# DeckardsHelper.net
KiCad netlist of a schematic drawn in EAGLE
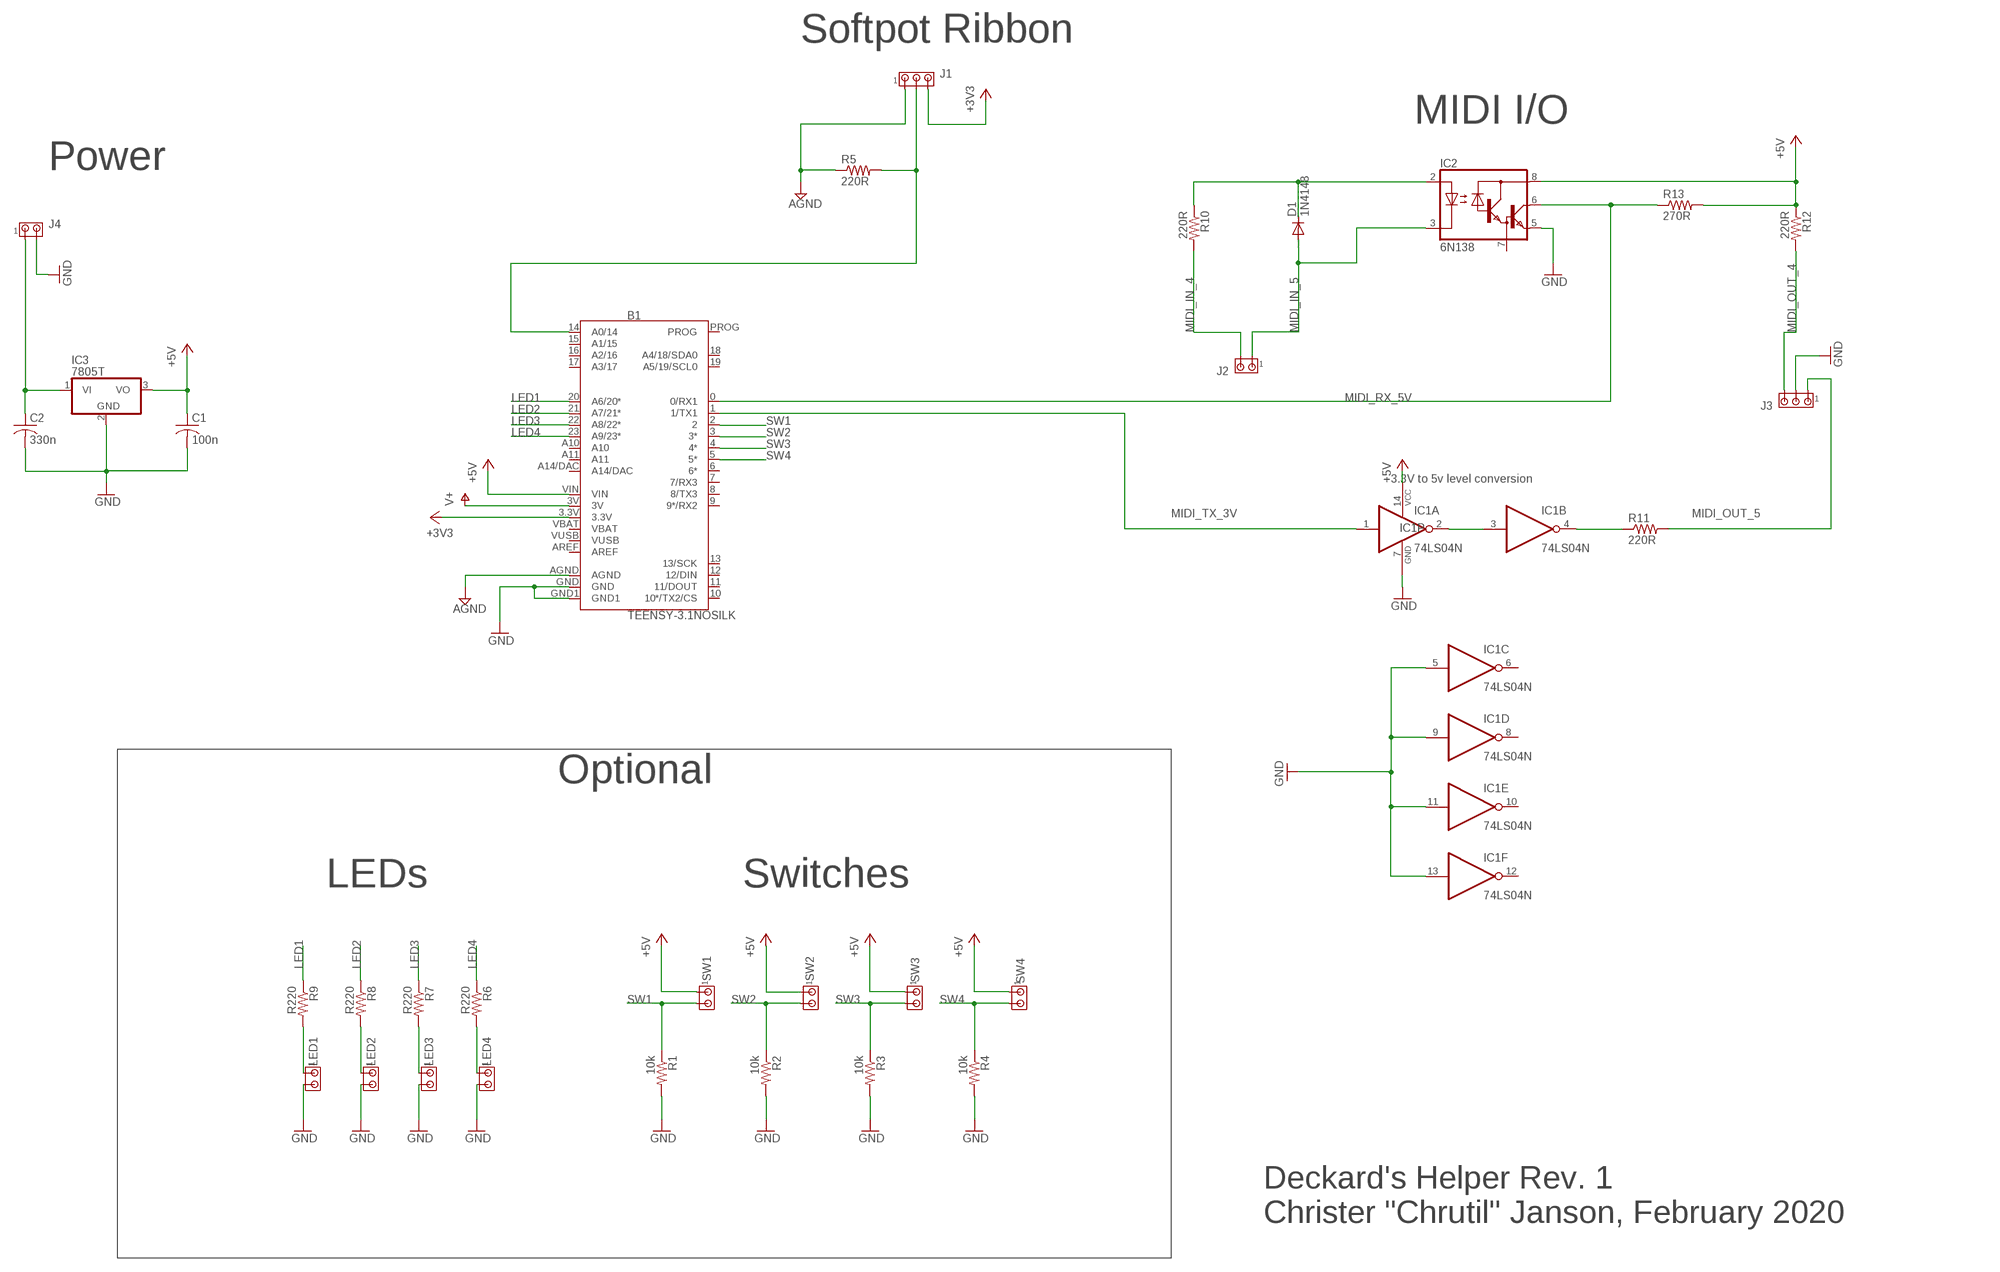
[diagram p0: schematic, sheet 1]

(export (version "E")
  (design (tool "Eeschema 10.0.6"))
  (components
    (comp (ref "B1")
      (value "TEENSY-3.1NOSILK")
      (footprint "eagle-import:TEENSY-3.1_NOSILK")
      (libsource (lib "eagle-import") (part "TEENSY-3.1NOSILK"))
    )
    (comp (ref "C1")
      (value "100n")
      (footprint "eagle-import:C025-025X050")
      (libsource (lib "eagle-import") (part "C-US025-025X050"))
    )
    (comp (ref "C2")
      (value "330n")
      (footprint "eagle-import:C025-025X050")
      (libsource (lib "eagle-import") (part "C-US025-025X050"))
    )
    (comp (ref "D1")
      (value "1N4148")
      (footprint "eagle-import:DO35-7")
      (libsource (lib "eagle-import") (part "1N4148DO35-7"))
    )
    (comp (ref "IC1")
      (value "74LS04N")
      (footprint "eagle-import:DIL14")
      (libsource (lib "eagle-import") (part "7404NLS"))
    )
    (comp (ref "IC2")
      (value "6N138")
      (footprint "eagle-import:DIL08")
      (fields (field (name "MF") "VISHAY/TELEFUNKEN"))
      (libsource (lib "eagle-import") (part "6N138"))
    )
    (comp (ref "IC3")
      (value "7805T")
      (footprint "eagle-import:TO220H")
      (libsource (lib "eagle-import") (part "78T05"))
    )
    (comp (ref "J1")
      (value "MTA03-100")
      (footprint "eagle-import:10X03MTA")
      (libsource (lib "eagle-import") (part "MTA03-100"))
    )
    (comp (ref "J2")
      (value "MTA02-100")
      (footprint "eagle-import:10X02MTA")
      (libsource (lib "eagle-import") (part "MTA02-100"))
    )
    (comp (ref "J3")
      (value "MTA03-100")
      (footprint "eagle-import:10X03MTA")
      (libsource (lib "eagle-import") (part "MTA03-100"))
    )
    (comp (ref "J4")
      (value "MTA02-100")
      (footprint "eagle-import:10X02MTA")
      (libsource (lib "eagle-import") (part "MTA02-100"))
    )
    (comp (ref "LED1")
      (value "MTA02-100")
      (footprint "eagle-import:10X02MTA")
      (libsource (lib "eagle-import") (part "MTA02-100"))
    )
    (comp (ref "LED2")
      (value "MTA02-100")
      (footprint "eagle-import:10X02MTA")
      (libsource (lib "eagle-import") (part "MTA02-100"))
    )
    (comp (ref "LED3")
      (value "MTA02-100")
      (footprint "eagle-import:10X02MTA")
      (libsource (lib "eagle-import") (part "MTA02-100"))
    )
    (comp (ref "LED4")
      (value "MTA02-100")
      (footprint "eagle-import:10X02MTA")
      (libsource (lib "eagle-import") (part "MTA02-100"))
    )
    (comp (ref "R1")
      (value "10k")
      (footprint "eagle-import:0204_7")
      (libsource (lib "eagle-import") (part "R-US_0204/7"))
    )
    (comp (ref "R2")
      (value "10k")
      (footprint "eagle-import:0204_7")
      (libsource (lib "eagle-import") (part "R-US_0204/7"))
    )
    (comp (ref "R3")
      (value "10k")
      (footprint "eagle-import:0204_7")
      (libsource (lib "eagle-import") (part "R-US_0204/7"))
    )
    (comp (ref "R4")
      (value "10k")
      (footprint "eagle-import:0204_7")
      (libsource (lib "eagle-import") (part "R-US_0204/7"))
    )
    (comp (ref "R5")
      (value "220R")
      (footprint "eagle-import:0204_7")
      (libsource (lib "eagle-import") (part "R-US_0204/7"))
    )
    (comp (ref "R6")
      (value "R220")
      (footprint "eagle-import:0204_7")
      (libsource (lib "eagle-import") (part "R-US_0204/7"))
    )
    (comp (ref "R7")
      (value "R220")
      (footprint "eagle-import:0204_7")
      (libsource (lib "eagle-import") (part "R-US_0204/7"))
    )
    (comp (ref "R8")
      (value "R220")
      (footprint "eagle-import:0204_7")
      (libsource (lib "eagle-import") (part "R-US_0204/7"))
    )
    (comp (ref "R9")
      (value "R220")
      (footprint "eagle-import:0204_7")
      (libsource (lib "eagle-import") (part "R-US_0204/7"))
    )
    (comp (ref "R10")
      (value "220R")
      (footprint "eagle-import:0204_7")
      (libsource (lib "eagle-import") (part "R-US_0204/7"))
    )
    (comp (ref "R11")
      (value "220R")
      (footprint "eagle-import:0204_7")
      (libsource (lib "eagle-import") (part "R-US_0204/7"))
    )
    (comp (ref "R12")
      (value "220R")
      (footprint "eagle-import:0204_7")
      (libsource (lib "eagle-import") (part "R-US_0204/7"))
    )
    (comp (ref "R13")
      (value "270R")
      (footprint "eagle-import:0204_7")
      (libsource (lib "eagle-import") (part "R-US_0204/7"))
    )
    (comp (ref "SW1")
      (value "MTA02-100")
      (footprint "eagle-import:10X02MTA")
      (libsource (lib "eagle-import") (part "MTA02-100"))
    )
    (comp (ref "SW2")
      (value "MTA02-100")
      (footprint "eagle-import:10X02MTA")
      (libsource (lib "eagle-import") (part "MTA02-100"))
    )
    (comp (ref "SW3")
      (value "MTA02-100")
      (footprint "eagle-import:10X02MTA")
      (libsource (lib "eagle-import") (part "MTA02-100"))
    )
    (comp (ref "SW4")
      (value "MTA02-100")
      (footprint "eagle-import:10X02MTA")
      (libsource (lib "eagle-import") (part "MTA02-100"))
    )
  )
  (nets
    (net (code "1") (name "+3V3") (class "Default")
      (node (ref "B1") (pin "3.3V") (pinfunction "3.3V_3.3V") (pintype "power_in"))
      (node (ref "J1") (pin "3") (pinfunction "3_3") (pintype "passive"))
    )
    (net (code "2") (name "+5V") (class "Default")
      (node (ref "B1") (pin "VIN") (pinfunction "VIN_VIN") (pintype "power_in"))
      (node (ref "C1") (pin "1") (pinfunction "1_1") (pintype "passive"))
      (node (ref "IC1") (pin "14") (pinfunction "VCC_14") (pintype "power_in"))
      (node (ref "IC2") (pin "8") (pinfunction "VCC_8") (pintype "passive"))
      (node (ref "IC3") (pin "3") (pinfunction "VO_3") (pintype "passive"))
      (node (ref "R12") (pin "1") (pinfunction "1_1") (pintype "passive"))
      (node (ref "R13") (pin "2") (pinfunction "2_2") (pintype "passive"))
      (node (ref "SW1") (pin "1") (pinfunction "1_1") (pintype "passive"))
      (node (ref "SW2") (pin "1") (pinfunction "1_1") (pintype "passive"))
      (node (ref "SW3") (pin "1") (pinfunction "1_1") (pintype "passive"))
      (node (ref "SW4") (pin "1") (pinfunction "1_1") (pintype "passive"))
    )
    (net (code "3") (name "/LED1") (class "Default")
      (node (ref "B1") (pin "20") (pinfunction "A6/20*_20") (pintype "bidirectional"))
      (node (ref "R9") (pin "1") (pinfunction "1_1") (pintype "passive"))
    )
    (net (code "4") (name "/LED2") (class "Default")
      (node (ref "B1") (pin "21") (pinfunction "A7/21*_21") (pintype "bidirectional"))
      (node (ref "R8") (pin "1") (pinfunction "1_1") (pintype "passive"))
    )
    (net (code "5") (name "/LED3") (class "Default")
      (node (ref "B1") (pin "22") (pinfunction "A8/22*_22") (pintype "bidirectional"))
      (node (ref "R7") (pin "1") (pinfunction "1_1") (pintype "passive"))
    )
    (net (code "6") (name "/LED4") (class "Default")
      (node (ref "B1") (pin "23") (pinfunction "A9/23*_23") (pintype "bidirectional"))
      (node (ref "R6") (pin "1") (pinfunction "1_1") (pintype "passive"))
    )
    (net (code "7") (name "/MIDI_IN_4") (class "Default")
      (node (ref "J2") (pin "2") (pinfunction "2_2") (pintype "passive"))
      (node (ref "R10") (pin "2") (pinfunction "2_2") (pintype "passive"))
    )
    (net (code "8") (name "/MIDI_IN_5") (class "Default")
      (node (ref "D1") (pin "A") (pinfunction "A_A") (pintype "passive"))
      (node (ref "IC2") (pin "3") (pinfunction "C_3") (pintype "passive"))
      (node (ref "J2") (pin "1") (pinfunction "1_1") (pintype "passive"))
    )
    (net (code "9") (name "/MIDI_OUT_4") (class "Default")
      (node (ref "J3") (pin "3") (pinfunction "3_3") (pintype "passive"))
      (node (ref "R12") (pin "2") (pinfunction "2_2") (pintype "passive"))
    )
    (net (code "10") (name "/MIDI_OUT_5") (class "Default")
      (node (ref "J3") (pin "1") (pinfunction "1_1") (pintype "passive"))
      (node (ref "R11") (pin "2") (pinfunction "2_2") (pintype "passive"))
    )
    (net (code "11") (name "/MIDI_RX_5V") (class "Default")
      (node (ref "B1") (pin "0") (pinfunction "0/RX1_0") (pintype "bidirectional"))
      (node (ref "IC2") (pin "6") (pinfunction "VO_6") (pintype "passive"))
      (node (ref "R13") (pin "1") (pinfunction "1_1") (pintype "passive"))
    )
    (net (code "12") (name "/MIDI_TX_3V") (class "Default")
      (node (ref "B1") (pin "1") (pinfunction "1/TX1_1") (pintype "bidirectional"))
      (node (ref "IC1") (pin "1") (pinfunction "I_1") (pintype "input"))
    )
    (net (code "13") (name "/SW1") (class "Default")
      (node (ref "B1") (pin "2") (pinfunction "2_2") (pintype "bidirectional"))
      (node (ref "R1") (pin "1") (pinfunction "1_1") (pintype "passive"))
      (node (ref "SW1") (pin "2") (pinfunction "2_2") (pintype "passive"))
    )
    (net (code "14") (name "/SW2") (class "Default")
      (node (ref "B1") (pin "3") (pinfunction "3*_3") (pintype "bidirectional"))
      (node (ref "R2") (pin "1") (pinfunction "1_1") (pintype "passive"))
      (node (ref "SW2") (pin "2") (pinfunction "2_2") (pintype "passive"))
    )
    (net (code "15") (name "/SW3") (class "Default")
      (node (ref "B1") (pin "4") (pinfunction "4*_4") (pintype "bidirectional"))
      (node (ref "R3") (pin "1") (pinfunction "1_1") (pintype "passive"))
      (node (ref "SW3") (pin "2") (pinfunction "2_2") (pintype "passive"))
    )
    (net (code "16") (name "/SW4") (class "Default")
      (node (ref "B1") (pin "5") (pinfunction "5*_5") (pintype "bidirectional"))
      (node (ref "R4") (pin "1") (pinfunction "1_1") (pintype "passive"))
      (node (ref "SW4") (pin "2") (pinfunction "2_2") (pintype "passive"))
    )
    (net (code "17") (name "/VBAT") (class "Default")
      (node (ref "B1") (pin "VBAT") (pinfunction "VBAT_VBAT") (pintype "power_in"))
    )
    (net (code "18") (name "/VUSB") (class "Default")
      (node (ref "B1") (pin "VUSB") (pinfunction "VUSB_VUSB") (pintype "power_in"))
    )
    (net (code "19") (name "AGND") (class "Default")
      (node (ref "B1") (pin "AGND") (pinfunction "AGND_AGND") (pintype "power_in"))
      (node (ref "J1") (pin "1") (pinfunction "1_1") (pintype "passive"))
      (node (ref "R5") (pin "1") (pinfunction "1_1") (pintype "passive"))
    )
    (net (code "20") (name "GND") (class "Default")
      (node (ref "B1") (pin "GND") (pinfunction "GND_GND") (pintype "power_in"))
      (node (ref "B1") (pin "GND1") (pinfunction "GND1_GND1") (pintype "power_in"))
      (node (ref "C1") (pin "2") (pinfunction "2_2") (pintype "passive"))
      (node (ref "C2") (pin "2") (pinfunction "2_2") (pintype "passive"))
      (node (ref "IC1") (pin "11") (pinfunction "I_11") (pintype "input"))
      (node (ref "IC1") (pin "13") (pinfunction "I_13") (pintype "input"))
      (node (ref "IC1") (pin "5") (pinfunction "I_5") (pintype "input"))
      (node (ref "IC1") (pin "7") (pinfunction "GND_7") (pintype "power_in"))
      (node (ref "IC1") (pin "9") (pinfunction "I_9") (pintype "input"))
      (node (ref "IC2") (pin "5") (pinfunction "GND_5") (pintype "passive"))
      (node (ref "IC3") (pin "2") (pinfunction "GND_2") (pintype "passive"))
      (node (ref "J3") (pin "2") (pinfunction "2_2") (pintype "passive"))
      (node (ref "J4") (pin "2") (pinfunction "2_2") (pintype "passive"))
      (node (ref "LED1") (pin "2") (pinfunction "2_2") (pintype "passive"))
      (node (ref "LED2") (pin "2") (pinfunction "2_2") (pintype "passive"))
      (node (ref "LED3") (pin "2") (pinfunction "2_2") (pintype "passive"))
      (node (ref "LED4") (pin "2") (pinfunction "2_2") (pintype "passive"))
      (node (ref "R1") (pin "2") (pinfunction "2_2") (pintype "passive"))
      (node (ref "R2") (pin "2") (pinfunction "2_2") (pintype "passive"))
      (node (ref "R3") (pin "2") (pinfunction "2_2") (pintype "passive"))
      (node (ref "R4") (pin "2") (pinfunction "2_2") (pintype "passive"))
    )
    (net (code "21") (name "Net-(B1-A0{slash}14)") (class "Default")
      (node (ref "B1") (pin "14") (pinfunction "A0/14_14") (pintype "bidirectional"))
      (node (ref "J1") (pin "2") (pinfunction "2_2") (pintype "passive"))
      (node (ref "R5") (pin "2") (pinfunction "2_2") (pintype "passive"))
    )
    (net (code "22") (name "Net-(IC1A-O)") (class "Default")
      (node (ref "IC1") (pin "2") (pinfunction "O_2") (pintype "output"))
      (node (ref "IC1") (pin "3") (pinfunction "I_3") (pintype "input"))
    )
    (net (code "23") (name "Net-(IC1B-O)") (class "Default")
      (node (ref "IC1") (pin "4") (pinfunction "O_4") (pintype "output"))
      (node (ref "R11") (pin "1") (pinfunction "1_1") (pintype "passive"))
    )
    (net (code "24") (name "Net-(IC2-A)") (class "Default")
      (node (ref "D1") (pin "C") (pinfunction "C_C") (pintype "passive"))
      (node (ref "IC2") (pin "2") (pinfunction "A_2") (pintype "passive"))
      (node (ref "R10") (pin "1") (pinfunction "1_1") (pintype "passive"))
    )
    (net (code "25") (name "Net-(IC3-VI)") (class "Default")
      (node (ref "C2") (pin "1") (pinfunction "1_1") (pintype "passive"))
      (node (ref "IC3") (pin "1") (pinfunction "VI_1") (pintype "input"))
      (node (ref "J4") (pin "1") (pinfunction "1_1") (pintype "passive"))
    )
    (net (code "26") (name "Net-(LED1-Pad1)") (class "Default")
      (node (ref "LED1") (pin "1") (pinfunction "1_1") (pintype "passive"))
      (node (ref "R9") (pin "2") (pinfunction "2_2") (pintype "passive"))
    )
    (net (code "27") (name "Net-(LED2-Pad1)") (class "Default")
      (node (ref "LED2") (pin "1") (pinfunction "1_1") (pintype "passive"))
      (node (ref "R8") (pin "2") (pinfunction "2_2") (pintype "passive"))
    )
    (net (code "28") (name "Net-(LED3-Pad1)") (class "Default")
      (node (ref "LED3") (pin "1") (pinfunction "1_1") (pintype "passive"))
      (node (ref "R7") (pin "2") (pinfunction "2_2") (pintype "passive"))
    )
    (net (code "29") (name "Net-(LED4-Pad1)") (class "Default")
      (node (ref "LED4") (pin "1") (pinfunction "1_1") (pintype "passive"))
      (node (ref "R6") (pin "2") (pinfunction "2_2") (pintype "passive"))
    )
    (net (code "30") (name "V+") (class "Default")
      (node (ref "B1") (pin "3V") (pinfunction "3V_3V") (pintype "power_in"))
    )
    (net (code "31") (name "unconnected-(B1-6*-Pad6)") (class "Default")
      (node (ref "B1") (pin "6") (pinfunction "6*_6") (pintype "bidirectional"))
    )
    (net (code "32") (name "unconnected-(B1-7{slash}RX3-Pad7)") (class "Default")
      (node (ref "B1") (pin "7") (pinfunction "7/RX3_7") (pintype "bidirectional"))
    )
    (net (code "33") (name "unconnected-(B1-8{slash}TX3-Pad8)") (class "Default")
      (node (ref "B1") (pin "8") (pinfunction "8/TX3_8") (pintype "bidirectional"))
    )
    (net (code "34") (name "unconnected-(B1-9*{slash}RX2-Pad9)") (class "Default")
      (node (ref "B1") (pin "9") (pinfunction "9*/RX2_9") (pintype "bidirectional"))
    )
    (net (code "35") (name "unconnected-(B1-10*{slash}TX2{slash}CS-Pad10)") (class "Default")
      (node (ref "B1") (pin "10") (pinfunction "10*/TX2/CS_10") (pintype "bidirectional"))
    )
    (net (code "36") (name "unconnected-(B1-11{slash}DOUT-Pad11)") (class "Default")
      (node (ref "B1") (pin "11") (pinfunction "11/DOUT_11") (pintype "bidirectional"))
    )
    (net (code "37") (name "unconnected-(B1-12{slash}DIN-Pad12)") (class "Default")
      (node (ref "B1") (pin "12") (pinfunction "12/DIN_12") (pintype "bidirectional"))
    )
    (net (code "38") (name "unconnected-(B1-13{slash}SCK-Pad13)") (class "Default")
      (node (ref "B1") (pin "13") (pinfunction "13/SCK_13") (pintype "bidirectional"))
    )
    (net (code "39") (name "unconnected-(B1-A1{slash}15-Pad15)") (class "Default")
      (node (ref "B1") (pin "15") (pinfunction "A1/15_15") (pintype "bidirectional"))
    )
    (net (code "40") (name "unconnected-(B1-A2{slash}16-Pad16)") (class "Default")
      (node (ref "B1") (pin "16") (pinfunction "A2/16_16") (pintype "bidirectional"))
    )
    (net (code "41") (name "unconnected-(B1-A3{slash}17-Pad17)") (class "Default")
      (node (ref "B1") (pin "17") (pinfunction "A3/17_17") (pintype "bidirectional"))
    )
    (net (code "42") (name "unconnected-(B1-A4{slash}18{slash}SDA0-Pad18)") (class "Default")
      (node (ref "B1") (pin "18") (pinfunction "A4/18/SDA0_18") (pintype "bidirectional"))
    )
    (net (code "43") (name "unconnected-(B1-A5{slash}19{slash}SCL0-Pad19)") (class "Default")
      (node (ref "B1") (pin "19") (pinfunction "A5/19/SCL0_19") (pintype "bidirectional"))
    )
    (net (code "44") (name "unconnected-(B1-PadA10)") (class "Default")
      (node (ref "B1") (pin "A10") (pinfunction "A10_A10") (pintype "bidirectional"))
    )
    (net (code "45") (name "unconnected-(B1-PadA11)") (class "Default")
      (node (ref "B1") (pin "A11") (pinfunction "A11_A11") (pintype "bidirectional"))
    )
    (net (code "46") (name "unconnected-(B1-PadA14{slash}DAC)") (class "Default")
      (node (ref "B1") (pin "A14/DAC") (pinfunction "A14/DAC_A14/DAC") (pintype "bidirectional"))
    )
    (net (code "47") (name "unconnected-(B1-PadAREF)") (class "Default")
      (node (ref "B1") (pin "AREF") (pinfunction "AREF_AREF") (pintype "bidirectional"))
    )
    (net (code "48") (name "unconnected-(B1-PadPROG)") (class "Default")
      (node (ref "B1") (pin "PROG") (pinfunction "PROG_PROG") (pintype "bidirectional"))
    )
    (net (code "49") (name "unconnected-(IC1C-O-Pad6)") (class "Default")
      (node (ref "IC1") (pin "6") (pinfunction "O_6") (pintype "output"))
    )
    (net (code "50") (name "unconnected-(IC1D-O-Pad8)") (class "Default")
      (node (ref "IC1") (pin "8") (pinfunction "O_8") (pintype "output"))
    )
    (net (code "51") (name "unconnected-(IC1E-O-Pad10)") (class "Default")
      (node (ref "IC1") (pin "10") (pinfunction "O_10") (pintype "output"))
    )
    (net (code "52") (name "unconnected-(IC1F-O-Pad12)") (class "Default")
      (node (ref "IC1") (pin "12") (pinfunction "O_12") (pintype "output"))
    )
    (net (code "53") (name "unconnected-(IC2-VB-Pad7)") (class "Default")
      (node (ref "IC2") (pin "7") (pinfunction "VB_7") (pintype "passive"))
    )
  )
)
